# megacommand23-oledpowerfix.net
KiCad netlist of a schematic drawn in EAGLE
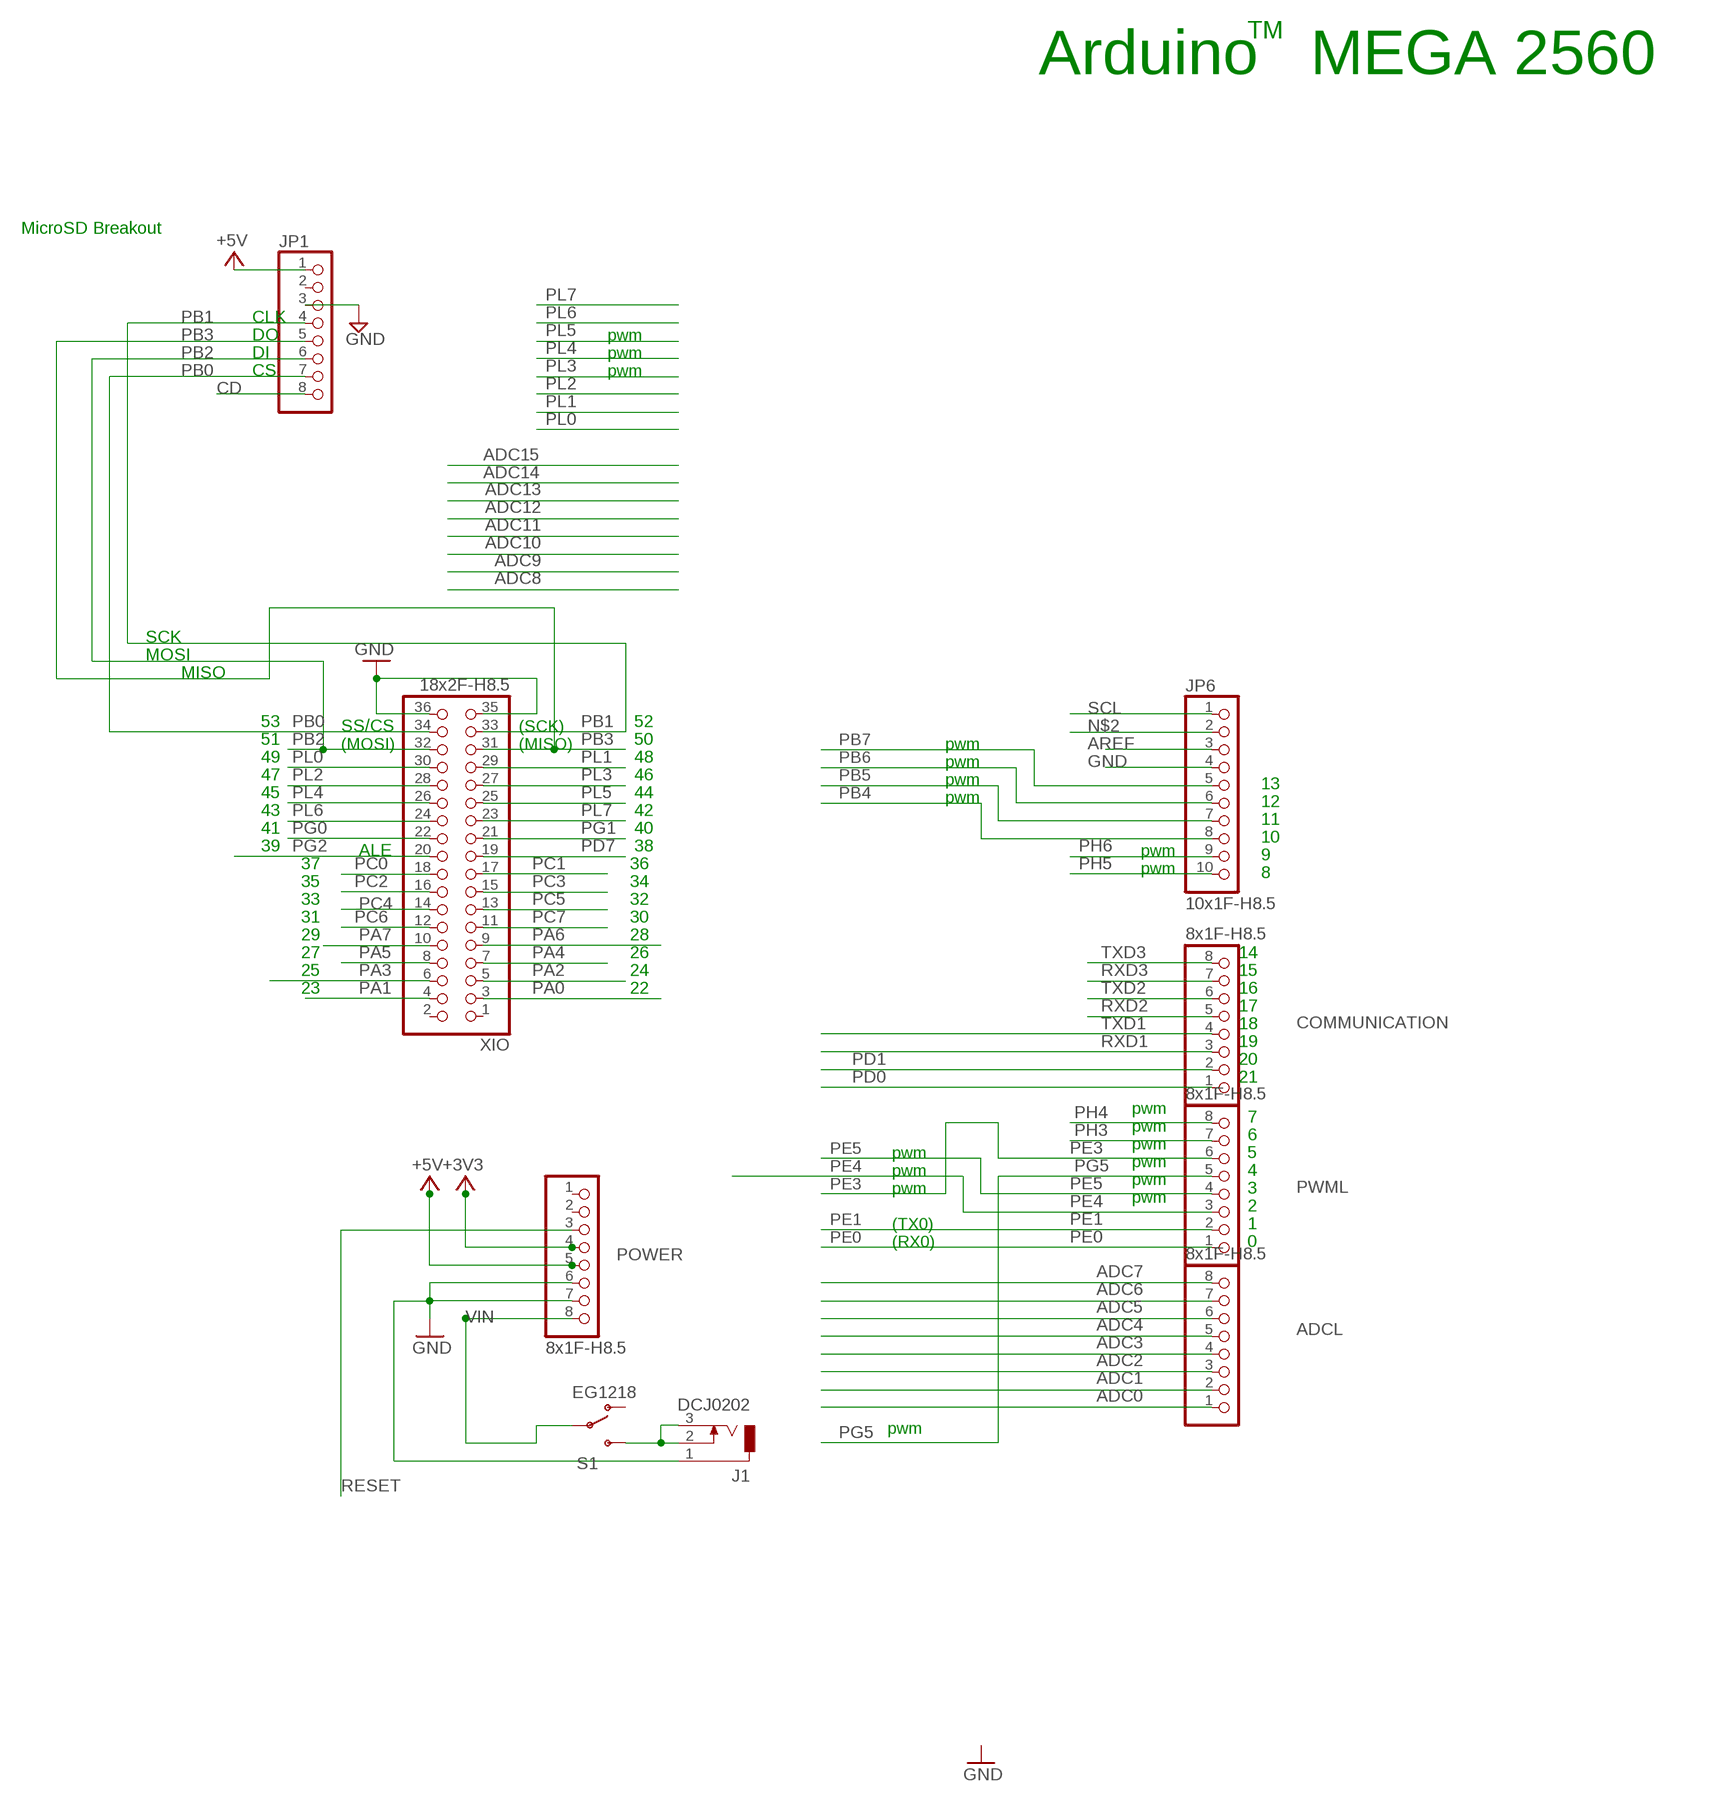
[diagram p0: schematic, sheet 1]
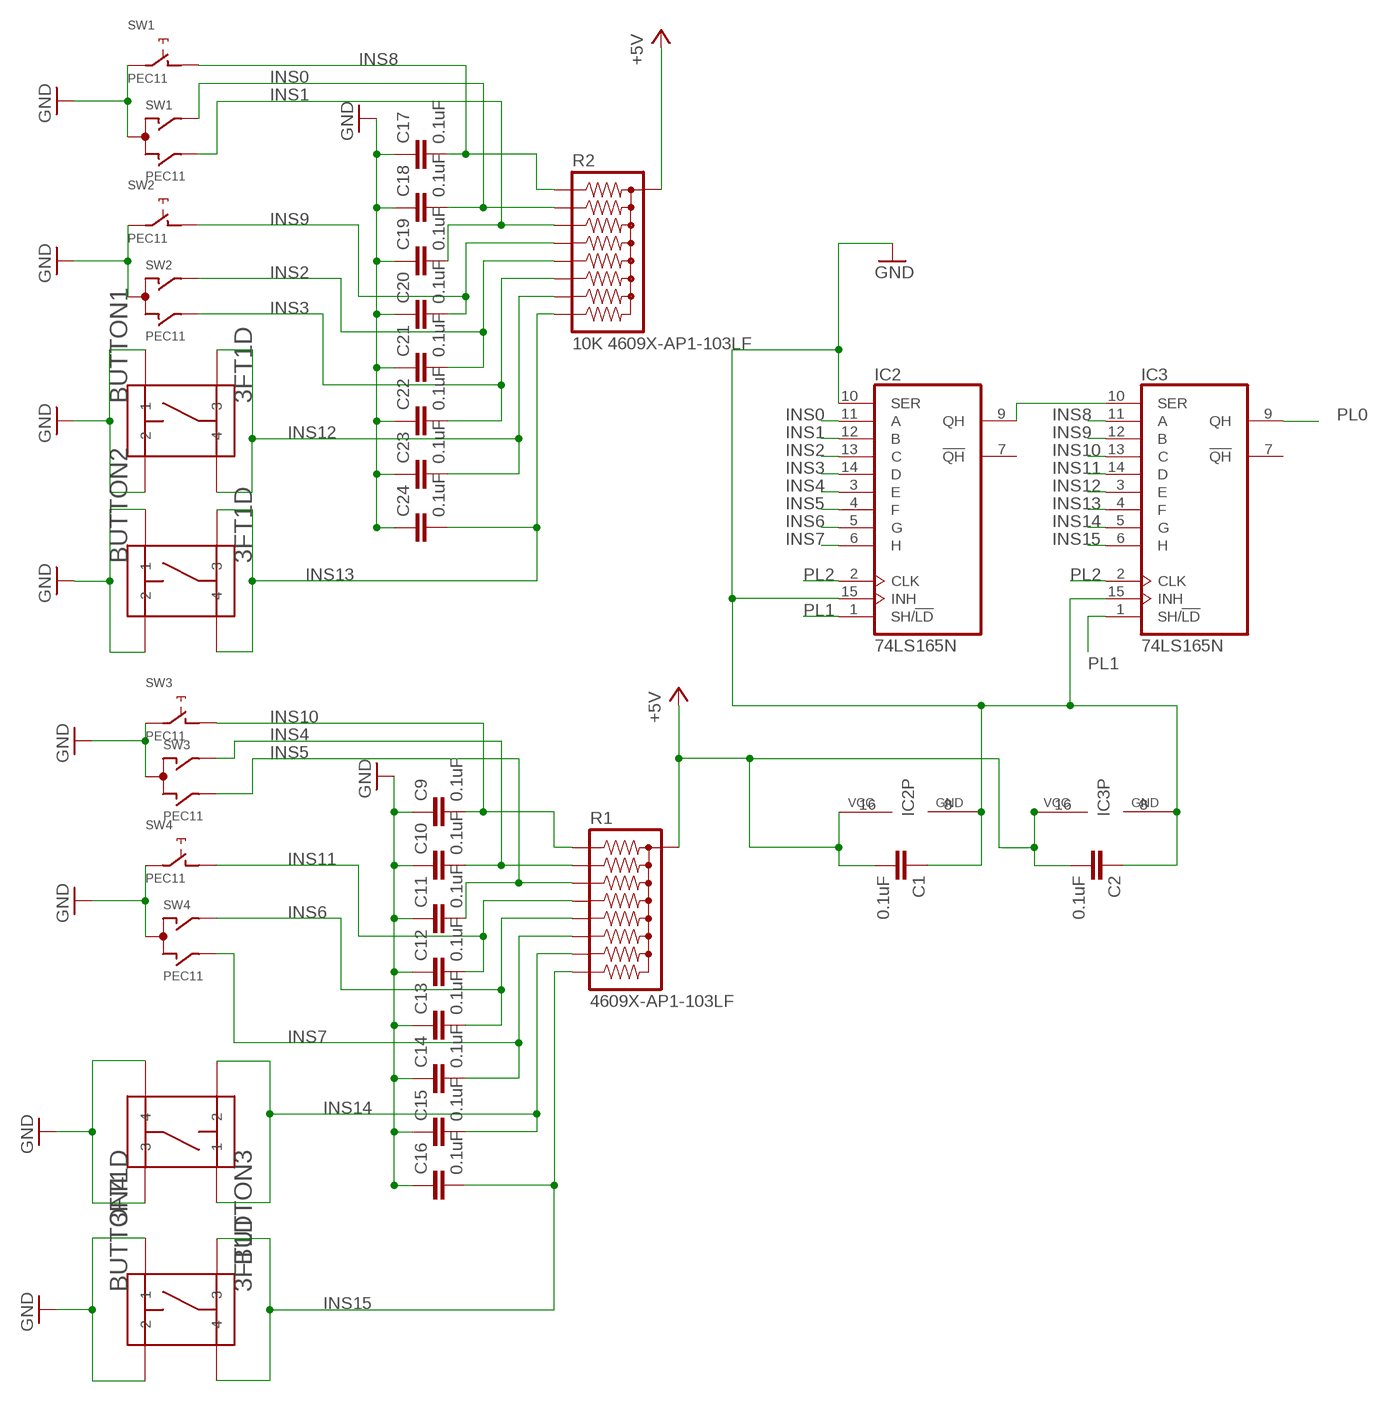
[diagram p1: schematic, sheet 2]
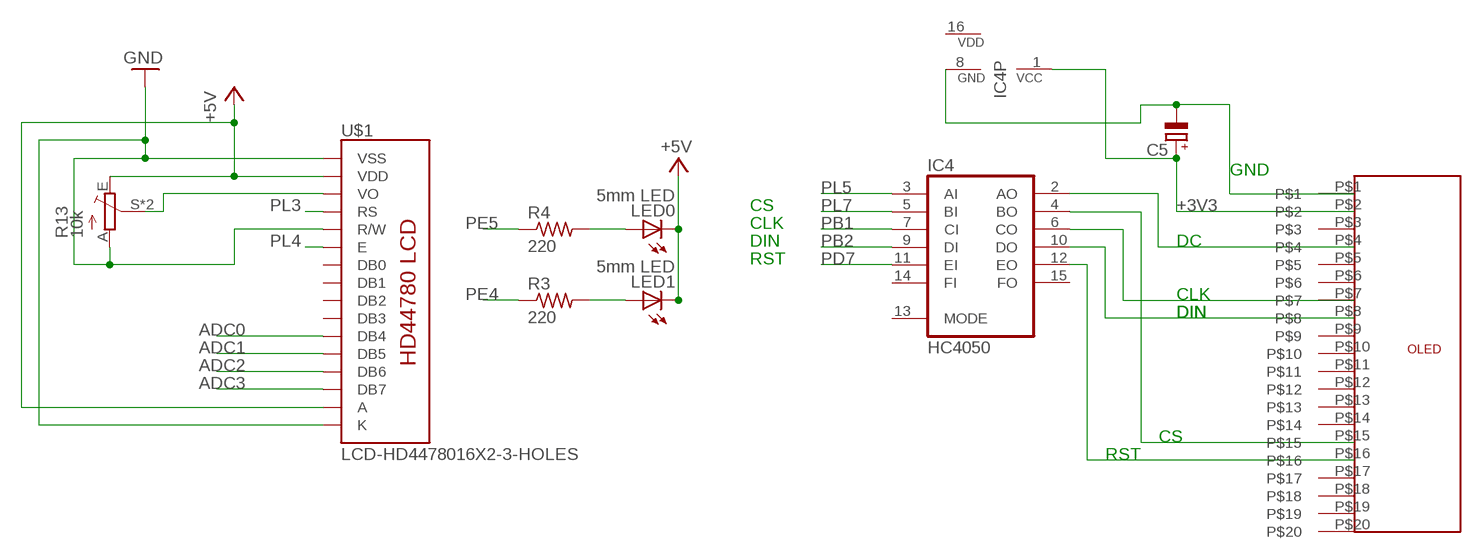
[diagram p2: schematic, sheet 3]
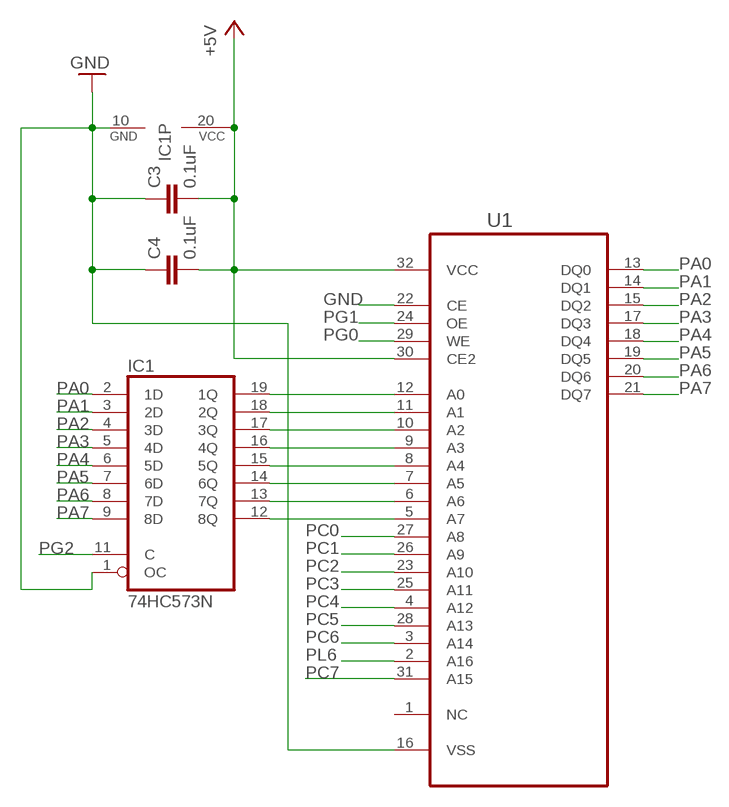
[diagram p3: schematic, sheet 4]
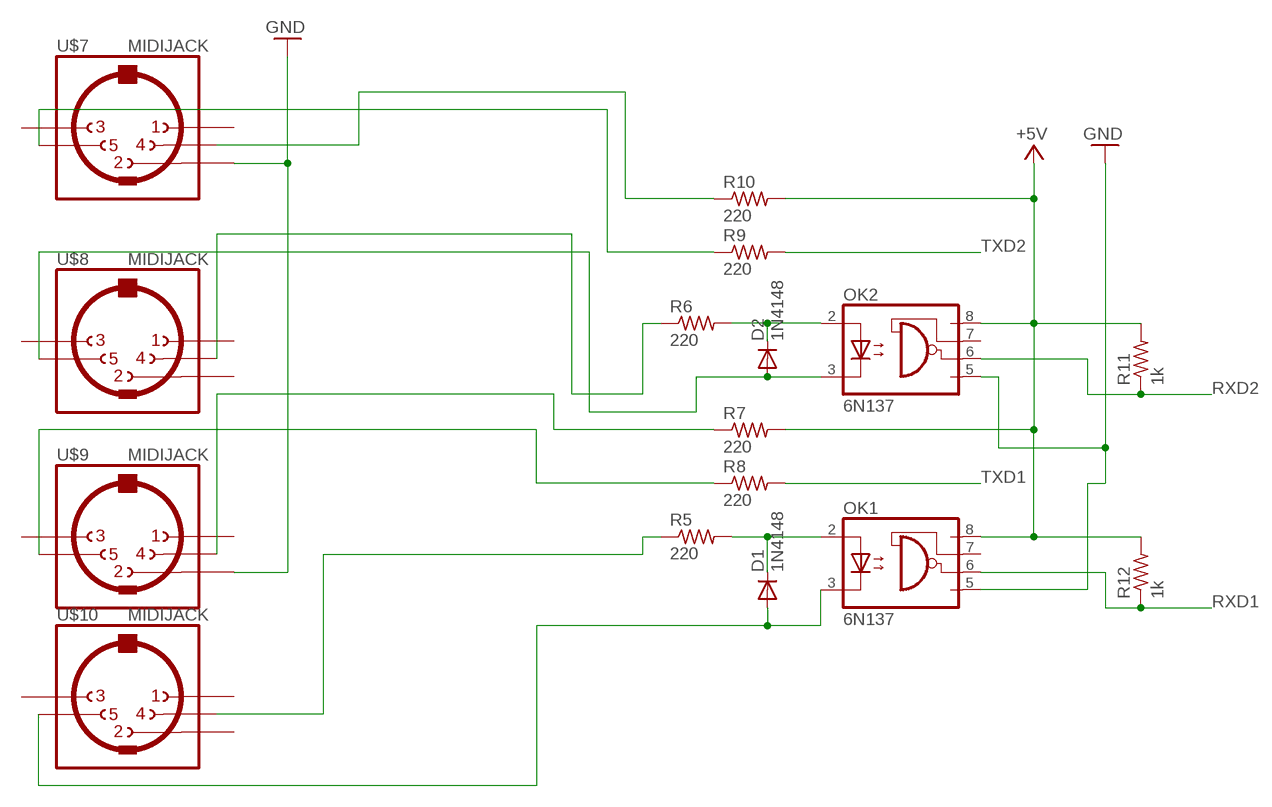
[diagram p4: schematic, sheet 5]

(export (version "E")
  (design (tool "Eeschema 10.0.6"))
  (components
    (comp (ref "C5")
      (value "CPOL-EUTT2D6")
      (footprint "eagle-import:TT2D6")
      (libsource (lib "eagle-import") (part "CPOL-EUTT2D6"))
    )
    (comp (ref "IC4")
      (value "HC4050")
      (footprint "eagle-import:DIL16")
      (libsource (lib "eagle-import") (part "4504N"))
    )
    (comp (ref "LED0")
      (value "5mm LED")
      (footprint "eagle-import:LED_LD260")
      (libsource (lib "eagle-import") (part "LED_ELD260"))
    )
    (comp (ref "LED1")
      (value "5mm LED")
      (footprint "eagle-import:LED_LD260")
      (libsource (lib "eagle-import") (part "LED_ELD260"))
    )
    (comp (ref "R3")
      (value "220")
      (footprint "eagle-import:0207_7")
      (libsource (lib "eagle-import") (part "R-US_0207/7"))
    )
    (comp (ref "R4")
      (value "220")
      (footprint "eagle-import:0207_7")
      (libsource (lib "eagle-import") (part "R-US_0207/7"))
    )
    (comp (ref "R13")
      (value "10k")
      (footprint "eagle-import:CA6V")
      (libsource (lib "eagle-import") (part "TRIM_EU-CA6V"))
    )
    (comp (ref "U$1")
      (value "LCD-HD4478016X2-3-HOLES")
      (footprint "eagle-import:LCD-16X2-3HOLES")
      (libsource (lib "eagle-import") (part "LCD-HD4478016X2-3-HOLES"))
    )
    (comp (ref "U$2")
      (value "20PIN")
      (footprint "eagle-import:20PIN")
      (libsource (lib "eagle-import") (part "20PIN"))
    )
    (comp (ref "D1")
      (value "1N4148")
      (footprint "eagle-import:DO35-7")
      (libsource (lib "eagle-import") (part "1N4148DO35-7"))
    )
    (comp (ref "D2")
      (value "1N4148")
      (footprint "eagle-import:DO35-7")
      (libsource (lib "eagle-import") (part "1N4148DO35-7"))
    )
    (comp (ref "OK1")
      (value "6N137")
      (footprint "eagle-import:DIL08")
      (libsource (lib "eagle-import") (part "6N137"))
    )
    (comp (ref "OK2")
      (value "6N137")
      (footprint "eagle-import:DIL08")
      (libsource (lib "eagle-import") (part "6N137"))
    )
    (comp (ref "R5")
      (value "220")
      (footprint "eagle-import:0207_7")
      (libsource (lib "eagle-import") (part "R-US_0207/7"))
    )
    (comp (ref "R6")
      (value "220")
      (footprint "eagle-import:0207_7")
      (libsource (lib "eagle-import") (part "R-US_0207/7"))
    )
    (comp (ref "R7")
      (value "220")
      (footprint "eagle-import:0207_7")
      (libsource (lib "eagle-import") (part "R-US_0207/7"))
    )
    (comp (ref "R8")
      (value "220")
      (footprint "eagle-import:0207_7")
      (libsource (lib "eagle-import") (part "R-US_0207/7"))
    )
    (comp (ref "R9")
      (value "220")
      (footprint "eagle-import:0207_7")
      (libsource (lib "eagle-import") (part "R-US_0207/7"))
    )
    (comp (ref "R10")
      (value "220")
      (footprint "eagle-import:0207_7")
      (libsource (lib "eagle-import") (part "R-US_0207/7"))
    )
    (comp (ref "R11")
      (value "1k")
      (footprint "eagle-import:0207_7")
      (libsource (lib "eagle-import") (part "R-US_0207/7"))
    )
    (comp (ref "R12")
      (value "1k")
      (footprint "eagle-import:0207_7")
      (libsource (lib "eagle-import") (part "R-US_0207/7"))
    )
    (comp (ref "U$7")
      (value "MIDIJACK")
      (footprint "eagle-import:CP-2350")
      (libsource (lib "eagle-import") (part "MIDIJACK"))
    )
    (comp (ref "U$8")
      (value "MIDIJACK")
      (footprint "eagle-import:CP-2350")
      (libsource (lib "eagle-import") (part "MIDIJACK"))
    )
    (comp (ref "U$9")
      (value "MIDIJACK")
      (footprint "eagle-import:CP-2350")
      (libsource (lib "eagle-import") (part "MIDIJACK"))
    )
    (comp (ref "U$10")
      (value "MIDIJACK")
      (footprint "eagle-import:CP-2350")
      (libsource (lib "eagle-import") (part "MIDIJACK"))
    )
    (comp (ref "BUTTON1")
      (value "3FT1D")
      (footprint "eagle-import:3FT")
      (libsource (lib "eagle-import") (part "3FT1D"))
    )
    (comp (ref "BUTTON2")
      (value "3FT1D")
      (footprint "eagle-import:3FT")
      (libsource (lib "eagle-import") (part "3FT1D"))
    )
    (comp (ref "BUTTON3")
      (value "3FT1D")
      (footprint "eagle-import:3FT")
      (libsource (lib "eagle-import") (part "3FT1D"))
    )
    (comp (ref "BUTTON4")
      (value "3FT1D")
      (footprint "eagle-import:3FT")
      (libsource (lib "eagle-import") (part "3FT1D"))
    )
    (comp (ref "C1")
      (value "0.1uF")
      (footprint "eagle-import:C025-050X050")
      (libsource (lib "eagle-import") (part "C-EU025-050X050"))
    )
    (comp (ref "C2")
      (value "0.1uF")
      (footprint "eagle-import:C025-050X050")
      (libsource (lib "eagle-import") (part "C-EU025-050X050"))
    )
    (comp (ref "C9")
      (value "0.1uF")
      (footprint "eagle-import:C025-050X050")
      (libsource (lib "eagle-import") (part "C-EU025-050X050"))
    )
    (comp (ref "C10")
      (value "0.1uF")
      (footprint "eagle-import:C025-050X050")
      (libsource (lib "eagle-import") (part "C-EU025-050X050"))
    )
    (comp (ref "C11")
      (value "0.1uF")
      (footprint "eagle-import:C025-050X050")
      (libsource (lib "eagle-import") (part "C-EU025-050X050"))
    )
    (comp (ref "C12")
      (value "0.1uF")
      (footprint "eagle-import:C025-050X050")
      (libsource (lib "eagle-import") (part "C-EU025-050X050"))
    )
    (comp (ref "C13")
      (value "0.1uF")
      (footprint "eagle-import:C025-050X050")
      (libsource (lib "eagle-import") (part "C-EU025-050X050"))
    )
    (comp (ref "C14")
      (value "0.1uF")
      (footprint "eagle-import:C025-050X050")
      (libsource (lib "eagle-import") (part "C-EU025-050X050"))
    )
    (comp (ref "C15")
      (value "0.1uF")
      (footprint "eagle-import:C025-050X050")
      (libsource (lib "eagle-import") (part "C-EU025-050X050"))
    )
    (comp (ref "C16")
      (value "0.1uF")
      (footprint "eagle-import:C025-050X050")
      (libsource (lib "eagle-import") (part "C-EU025-050X050"))
    )
    (comp (ref "C17")
      (value "0.1uF")
      (footprint "eagle-import:C025-050X050")
      (libsource (lib "eagle-import") (part "C-EU025-050X050"))
    )
    (comp (ref "C18")
      (value "0.1uF")
      (footprint "eagle-import:C025-050X050")
      (libsource (lib "eagle-import") (part "C-EU025-050X050"))
    )
    (comp (ref "C19")
      (value "0.1uF")
      (footprint "eagle-import:C025-050X050")
      (libsource (lib "eagle-import") (part "C-EU025-050X050"))
    )
    (comp (ref "C20")
      (value "0.1uF")
      (footprint "eagle-import:C025-050X050")
      (libsource (lib "eagle-import") (part "C-EU025-050X050"))
    )
    (comp (ref "C21")
      (value "0.1uF")
      (footprint "eagle-import:C025-050X050")
      (libsource (lib "eagle-import") (part "C-EU025-050X050"))
    )
    (comp (ref "C22")
      (value "0.1uF")
      (footprint "eagle-import:C025-050X050")
      (libsource (lib "eagle-import") (part "C-EU025-050X050"))
    )
    (comp (ref "C23")
      (value "0.1uF")
      (footprint "eagle-import:C025-050X050")
      (libsource (lib "eagle-import") (part "C-EU025-050X050"))
    )
    (comp (ref "C24")
      (value "0.1uF")
      (footprint "eagle-import:C025-050X050")
      (libsource (lib "eagle-import") (part "C-EU025-050X050"))
    )
    (comp (ref "IC2")
      (value "74LS165N")
      (footprint "eagle-import:DIL16")
      (libsource (lib "eagle-import") (part "74165NLS"))
    )
    (comp (ref "IC3")
      (value "74LS165N")
      (footprint "eagle-import:DIL16")
      (libsource (lib "eagle-import") (part "74165NLS"))
    )
    (comp (ref "R1")
      (value "4609X-AP1-103LF")
      (footprint "eagle-import:RPACK-SIP-PTH-8")
      (libsource (lib "eagle-import") (part "RPACK-BUSSED-8-SIP-PTH-8"))
    )
    (comp (ref "R2")
      (value "10K 4609X-AP1-103LF")
      (footprint "eagle-import:RPACK-SIP-PTH-8")
      (libsource (lib "eagle-import") (part "RPACK-BUSSED-8-SIP-PTH-8"))
    )
    (comp (ref "SW1")
      (value "PEC11")
      (footprint "eagle-import:ALPS_EC12E_SW")
      (fields (field (name "MPN") "EC12E2424407"))
      (libsource (lib "eagle-import") (part "EC12E_SW"))
    )
    (comp (ref "SW2")
      (value "PEC11")
      (footprint "eagle-import:ALPS_EC12E_SW")
      (fields (field (name "MPN") "EC12E2424407"))
      (libsource (lib "eagle-import") (part "EC12E_SW"))
    )
    (comp (ref "SW3")
      (value "PEC11")
      (footprint "eagle-import:ALPS_EC12E_SW")
      (fields (field (name "MPN") "EC12E2424407"))
      (libsource (lib "eagle-import") (part "EC12E_SW"))
    )
    (comp (ref "SW4")
      (value "PEC11")
      (footprint "eagle-import:ALPS_EC12E_SW")
      (fields (field (name "MPN") "EC12E2424407"))
      (libsource (lib "eagle-import") (part "EC12E_SW"))
    )
    (comp (ref "C3")
      (value "0.1uF")
      (footprint "eagle-import:C025-050X050")
      (libsource (lib "eagle-import") (part "C-EU025-050X050"))
    )
    (comp (ref "C4")
      (value "0.1uF")
      (footprint "eagle-import:C025-050X050")
      (libsource (lib "eagle-import") (part "C-EU025-050X050"))
    )
    (comp (ref "IC1")
      (value "74HC573N")
      (footprint "eagle-import:DIL20")
      (libsource (lib "eagle-import") (part "74573NHC"))
    )
    (comp (ref "U1")
      (value "AS6C1008-55PCN")
      (footprint "eagle-import:DIP254P1524X393-32")
      (libsource (lib "eagle-import") (part "AS6C1008-55PCN"))
    )
    (comp (ref "ADCL")
      (value "8x1F-H8.5")
      (footprint "eagle-import:1X08")
      (libsource (lib "eagle-import") (part "PINHD-1X8"))
    )
    (comp (ref "COMMUNICATION")
      (value "8x1F-H8.5")
      (footprint "eagle-import:1X08")
      (libsource (lib "eagle-import") (part "PINHD-1X8"))
    )
    (comp (ref "J1")
      (value "DCJ0202")
      (footprint "eagle-import:DCJ0202")
      (libsource (lib "eagle-import") (part "DCJ0202"))
    )
    (comp (ref "JP1")
      (value "PINHD-1X8BIG")
      (footprint "eagle-import:1X08-BIG")
      (libsource (lib "eagle-import") (part "PINHD-1X8BIG"))
    )
    (comp (ref "JP6")
      (value "10x1F-H8.5")
      (footprint "eagle-import:1X10")
      (libsource (lib "eagle-import") (part "PINHD-1X10_ARD"))
    )
    (comp (ref "POWER")
      (value "8x1F-H8.5")
      (footprint "eagle-import:1X08")
      (libsource (lib "eagle-import") (part "PINHD-1X8"))
    )
    (comp (ref "PWML")
      (value "8x1F-H8.5")
      (footprint "eagle-import:1X08")
      (libsource (lib "eagle-import") (part "PINHD-1X8"))
    )
    (comp (ref "S1")
      (value "EG1218")
      (footprint "eagle-import:SWITCH-SPDT_KIT")
      (libsource (lib "eagle-import") (part "SWITCH-SPDTKIT"))
    )
    (comp (ref "XIO")
      (value "18x2F-H8.5")
      (footprint "eagle-import:2X18")
      (libsource (lib "eagle-import") (part "PINHD-2X18"))
    )
  )
  (nets
    (net (code "1") (name "+3V3") (class "Default")
      (node (ref "C5") (pin "+") (pinfunction "+_+") (pintype "passive"))
      (node (ref "IC4") (pin "1") (pinfunction "VCC_1") (pintype "power_in"))
      (node (ref "POWER") (pin "4") (pinfunction "4_4") (pintype "passive"))
      (node (ref "U$2") (pin "P$2") (pinfunction "P$2_P$2") (pintype "bidirectional"))
    )
    (net (code "2") (name "+5V") (class "Default")
      (node (ref "C1") (pin "2") (pinfunction "2_2") (pintype "passive"))
      (node (ref "C2") (pin "2") (pinfunction "2_2") (pintype "passive"))
      (node (ref "C3") (pin "2") (pinfunction "2_2") (pintype "passive"))
      (node (ref "C4") (pin "2") (pinfunction "2_2") (pintype "passive"))
      (node (ref "IC1") (pin "20") (pinfunction "VCC_20") (pintype "power_in"))
      (node (ref "IC2") (pin "16") (pinfunction "VCC_16") (pintype "power_in"))
      (node (ref "IC3") (pin "16") (pinfunction "VCC_16") (pintype "power_in"))
      (node (ref "JP1") (pin "1") (pinfunction "1_1") (pintype "passive"))
      (node (ref "LED0") (pin "K") (pinfunction "C_K") (pintype "passive"))
      (node (ref "LED1") (pin "K") (pinfunction "C_K") (pintype "passive"))
      (node (ref "OK1") (pin "8") (pinfunction "VCC_8") (pintype "passive"))
      (node (ref "OK2") (pin "8") (pinfunction "VCC_8") (pintype "passive"))
      (node (ref "POWER") (pin "5") (pinfunction "5_5") (pintype "passive"))
      (node (ref "R1") (pin "P$1") (pinfunction "1_P$1") (pintype "passive"))
      (node (ref "R10") (pin "2") (pinfunction "2_2") (pintype "passive"))
      (node (ref "R11") (pin "2") (pinfunction "2_2") (pintype "passive"))
      (node (ref "R12") (pin "2") (pinfunction "2_2") (pintype "passive"))
      (node (ref "R13") (pin "E") (pinfunction "E_E") (pintype "passive"))
      (node (ref "R2") (pin "P$1") (pinfunction "1_P$1") (pintype "passive"))
      (node (ref "R7") (pin "2") (pinfunction "2_2") (pintype "passive"))
      (node (ref "U$1") (pin "15") (pinfunction "A_15") (pintype "power_in"))
      (node (ref "U$1") (pin "2") (pinfunction "VDD_2") (pintype "power_in"))
      (node (ref "U1") (pin "30") (pinfunction "CE2_30") (pintype "input"))
      (node (ref "U1") (pin "32") (pinfunction "VCC_32") (pintype "power_in"))
    )
    (net (code "3") (name "ADC0") (class "Default")
      (node (ref "ADCL") (pin "1") (pinfunction "1_1") (pintype "passive"))
      (node (ref "U$1") (pin "11") (pinfunction "DB4_11") (pintype "bidirectional"))
    )
    (net (code "4") (name "ADC1") (class "Default")
      (node (ref "ADCL") (pin "2") (pinfunction "2_2") (pintype "passive"))
      (node (ref "U$1") (pin "12") (pinfunction "DB5_12") (pintype "bidirectional"))
    )
    (net (code "5") (name "ADC2") (class "Default")
      (node (ref "ADCL") (pin "3") (pinfunction "3_3") (pintype "passive"))
      (node (ref "U$1") (pin "13") (pinfunction "DB6_13") (pintype "bidirectional"))
    )
    (net (code "6") (name "ADC3") (class "Default")
      (node (ref "ADCL") (pin "4") (pinfunction "4_4") (pintype "passive"))
      (node (ref "U$1") (pin "14") (pinfunction "DB7_14") (pintype "bidirectional"))
    )
    (net (code "7") (name "ADC4") (class "Default")
      (node (ref "ADCL") (pin "5") (pinfunction "5_5") (pintype "passive"))
    )
    (net (code "8") (name "ADC5") (class "Default")
      (node (ref "ADCL") (pin "6") (pinfunction "6_6") (pintype "passive"))
    )
    (net (code "9") (name "ADC6") (class "Default")
      (node (ref "ADCL") (pin "7") (pinfunction "7_7") (pintype "passive"))
    )
    (net (code "10") (name "ADC7") (class "Default")
      (node (ref "ADCL") (pin "8") (pinfunction "8_8") (pintype "passive"))
    )
    (net (code "19") (name "AREF") (class "Default")
      (node (ref "JP6") (pin "3") (pinfunction "3_3") (pintype "passive"))
    )
    (net (code "20") (name "CD") (class "Default")
      (node (ref "JP1") (pin "8") (pinfunction "8_8") (pintype "passive"))
    )
    (net (code "21") (name "GND") (class "Default")
      (node (ref "BUTTON1") (pin "P$1") (pinfunction "1_P$1") (pintype "bidirectional"))
      (node (ref "BUTTON1") (pin "P$2") (pinfunction "2_P$2") (pintype "bidirectional"))
      (node (ref "BUTTON2") (pin "P$1") (pinfunction "1_P$1") (pintype "bidirectional"))
      (node (ref "BUTTON2") (pin "P$2") (pinfunction "2_P$2") (pintype "bidirectional"))
      (node (ref "BUTTON3") (pin "P$3") (pinfunction "3_P$3") (pintype "bidirectional"))
      (node (ref "BUTTON3") (pin "P$4") (pinfunction "4_P$4") (pintype "bidirectional"))
      (node (ref "BUTTON4") (pin "P$1") (pinfunction "1_P$1") (pintype "bidirectional"))
      (node (ref "BUTTON4") (pin "P$2") (pinfunction "2_P$2") (pintype "bidirectional"))
      (node (ref "C1") (pin "1") (pinfunction "1_1") (pintype "passive"))
      (node (ref "C10") (pin "1") (pinfunction "1_1") (pintype "passive"))
      (node (ref "C11") (pin "1") (pinfunction "1_1") (pintype "passive"))
      (node (ref "C12") (pin "1") (pinfunction "1_1") (pintype "passive"))
      (node (ref "C13") (pin "1") (pinfunction "1_1") (pintype "passive"))
      (node (ref "C14") (pin "1") (pinfunction "1_1") (pintype "passive"))
      (node (ref "C15") (pin "1") (pinfunction "1_1") (pintype "passive"))
      (node (ref "C16") (pin "1") (pinfunction "1_1") (pintype "passive"))
      (node (ref "C17") (pin "1") (pinfunction "1_1") (pintype "passive"))
      (node (ref "C18") (pin "1") (pinfunction "1_1") (pintype "passive"))
      (node (ref "C19") (pin "1") (pinfunction "1_1") (pintype "passive"))
      (node (ref "C2") (pin "1") (pinfunction "1_1") (pintype "passive"))
      (node (ref "C20") (pin "1") (pinfunction "1_1") (pintype "passive"))
      (node (ref "C21") (pin "1") (pinfunction "1_1") (pintype "passive"))
      (node (ref "C22") (pin "1") (pinfunction "1_1") (pintype "passive"))
      (node (ref "C23") (pin "1") (pinfunction "1_1") (pintype "passive"))
      (node (ref "C24") (pin "1") (pinfunction "1_1") (pintype "passive"))
      (node (ref "C3") (pin "1") (pinfunction "1_1") (pintype "passive"))
      (node (ref "C4") (pin "1") (pinfunction "1_1") (pintype "passive"))
      (node (ref "C5") (pin "-") (pinfunction "-_-") (pintype "passive"))
      (node (ref "C9") (pin "1") (pinfunction "1_1") (pintype "passive"))
      (node (ref "IC1") (pin "1") (pinfunction "OC_1") (pintype "input"))
      (node (ref "IC1") (pin "10") (pinfunction "GND_10") (pintype "power_in"))
      (node (ref "IC2") (pin "10") (pinfunction "SER_10") (pintype "input"))
      (node (ref "IC2") (pin "15") (pinfunction "INH_15") (pintype "input"))
      (node (ref "IC2") (pin "8") (pinfunction "GND_8") (pintype "power_in"))
      (node (ref "IC3") (pin "15") (pinfunction "INH_15") (pintype "input"))
      (node (ref "IC3") (pin "8") (pinfunction "GND_8") (pintype "power_in"))
      (node (ref "IC4") (pin "8") (pinfunction "GND_8") (pintype "power_in"))
      (node (ref "J1") (pin "1") (pinfunction "1_1") (pintype "passive"))
      (node (ref "JP1") (pin "3") (pinfunction "3_3") (pintype "passive"))
      (node (ref "JP6") (pin "4") (pinfunction "4_4") (pintype "passive"))
      (node (ref "OK1") (pin "5") (pinfunction "GND_5") (pintype "passive"))
      (node (ref "OK2") (pin "5") (pinfunction "GND_5") (pintype "passive"))
      (node (ref "POWER") (pin "6") (pinfunction "6_6") (pintype "passive"))
      (node (ref "POWER") (pin "7") (pinfunction "7_7") (pintype "passive"))
      (node (ref "R13") (pin "A") (pinfunction "A_A") (pintype "passive"))
      (node (ref "SW1") (pin "C") (pinfunction "C_C") (pintype "passive"))
      (node (ref "SW1") (pin "E") (pinfunction "2_E") (pintype "passive"))
      (node (ref "SW2") (pin "C") (pinfunction "C_C") (pintype "passive"))
      (node (ref "SW2") (pin "E") (pinfunction "2_E") (pintype "passive"))
      (node (ref "SW3") (pin "C") (pinfunction "C_C") (pintype "passive"))
      (node (ref "SW3") (pin "E") (pinfunction "2_E") (pintype "passive"))
      (node (ref "SW4") (pin "C") (pinfunction "C_C") (pintype "passive"))
      (node (ref "SW4") (pin "E") (pinfunction "2_E") (pintype "passive"))
      (node (ref "U$1") (pin "1") (pinfunction "VSS_1") (pintype "power_in"))
      (node (ref "U$1") (pin "16") (pinfunction "K_16") (pintype "power_in"))
      (node (ref "U$1") (pin "5") (pinfunction "R/W_5") (pintype "input"))
      (node (ref "U$2") (pin "P$1") (pinfunction "P$1_P$1") (pintype "bidirectional"))
      (node (ref "U$7") (pin "2") (pinfunction "2_2") (pintype "passive"))
      (node (ref "U$9") (pin "2") (pinfunction "2_2") (pintype "passive"))
      (node (ref "U1") (pin "16") (pinfunction "VSS_16") (pintype "bidirectional"))
      (node (ref "U1") (pin "22") (pinfunction "CE_22") (pintype "input"))
      (node (ref "XIO") (pin "35") (pinfunction "35_35") (pintype "passive"))
      (node (ref "XIO") (pin "36") (pinfunction "36_36") (pintype "passive"))
    )
    (net (code "22") (name "INS0") (class "Default")
      (node (ref "C18") (pin "2") (pinfunction "2_2") (pintype "passive"))
      (node (ref "IC2") (pin "11") (pinfunction "A_11") (pintype "input"))
      (node (ref "R2") (pin "P$3") (pinfunction "3_P$3") (pintype "passive"))
      (node (ref "SW1") (pin "A") (pinfunction "A_A") (pintype "passive"))
    )
    (net (code "23") (name "INS1") (class "Default")
      (node (ref "C19") (pin "2") (pinfunction "2_2") (pintype "passive"))
      (node (ref "IC2") (pin "12") (pinfunction "B_12") (pintype "input"))
      (node (ref "R2") (pin "P$4") (pinfunction "4_P$4") (pintype "passive"))
      (node (ref "SW1") (pin "B") (pinfunction "B_B") (pintype "passive"))
    )
    (net (code "24") (name "INS2") (class "Default")
      (node (ref "C21") (pin "2") (pinfunction "2_2") (pintype "passive"))
      (node (ref "IC2") (pin "13") (pinfunction "C_13") (pintype "input"))
      (node (ref "R2") (pin "P$6") (pinfunction "6_P$6") (pintype "passive"))
      (node (ref "SW2") (pin "A") (pinfunction "A_A") (pintype "passive"))
    )
    (net (code "25") (name "INS3") (class "Default")
      (node (ref "C22") (pin "2") (pinfunction "2_2") (pintype "passive"))
      (node (ref "IC2") (pin "14") (pinfunction "D_14") (pintype "input"))
      (node (ref "R2") (pin "P$7") (pinfunction "7_P$7") (pintype "passive"))
      (node (ref "SW2") (pin "B") (pinfunction "B_B") (pintype "passive"))
    )
    (net (code "26") (name "INS4") (class "Default")
      (node (ref "C10") (pin "2") (pinfunction "2_2") (pintype "passive"))
      (node (ref "IC2") (pin "3") (pinfunction "E_3") (pintype "input"))
      (node (ref "R1") (pin "P$3") (pinfunction "3_P$3") (pintype "passive"))
      (node (ref "SW3") (pin "A") (pinfunction "A_A") (pintype "passive"))
    )
    (net (code "27") (name "INS5") (class "Default")
      (node (ref "C11") (pin "2") (pinfunction "2_2") (pintype "passive"))
      (node (ref "IC2") (pin "4") (pinfunction "F_4") (pintype "input"))
      (node (ref "R1") (pin "P$4") (pinfunction "4_P$4") (pintype "passive"))
      (node (ref "SW3") (pin "B") (pinfunction "B_B") (pintype "passive"))
    )
    (net (code "28") (name "INS6") (class "Default")
      (node (ref "C13") (pin "2") (pinfunction "2_2") (pintype "passive"))
      (node (ref "IC2") (pin "5") (pinfunction "G_5") (pintype "input"))
      (node (ref "R1") (pin "P$6") (pinfunction "6_P$6") (pintype "passive"))
      (node (ref "SW4") (pin "A") (pinfunction "A_A") (pintype "passive"))
    )
    (net (code "29") (name "INS7") (class "Default")
      (node (ref "C14") (pin "2") (pinfunction "2_2") (pintype "passive"))
      (node (ref "IC2") (pin "6") (pinfunction "H_6") (pintype "input"))
      (node (ref "R1") (pin "P$7") (pinfunction "7_P$7") (pintype "passive"))
      (node (ref "SW4") (pin "B") (pinfunction "B_B") (pintype "passive"))
    )
    (net (code "30") (name "INS8") (class "Default")
      (node (ref "C17") (pin "2") (pinfunction "2_2") (pintype "passive"))
      (node (ref "IC3") (pin "11") (pinfunction "A_11") (pintype "input"))
      (node (ref "R2") (pin "P$2") (pinfunction "2_P$2") (pintype "passive"))
      (node (ref "SW1") (pin "D") (pinfunction "1_D") (pintype "passive"))
    )
    (net (code "31") (name "INS9") (class "Default")
      (node (ref "C20") (pin "2") (pinfunction "2_2") (pintype "passive"))
      (node (ref "IC3") (pin "12") (pinfunction "B_12") (pintype "input"))
      (node (ref "R2") (pin "P$5") (pinfunction "5_P$5") (pintype "passive"))
      (node (ref "SW2") (pin "D") (pinfunction "1_D") (pintype "passive"))
    )
    (net (code "32") (name "INS10") (class "Default")
      (node (ref "C9") (pin "2") (pinfunction "2_2") (pintype "passive"))
      (node (ref "IC3") (pin "13") (pinfunction "C_13") (pintype "input"))
      (node (ref "R1") (pin "P$2") (pinfunction "2_P$2") (pintype "passive"))
      (node (ref "SW3") (pin "D") (pinfunction "1_D") (pintype "passive"))
    )
    (net (code "33") (name "INS11") (class "Default")
      (node (ref "C12") (pin "2") (pinfunction "2_2") (pintype "passive"))
      (node (ref "IC3") (pin "14") (pinfunction "D_14") (pintype "input"))
      (node (ref "R1") (pin "P$5") (pinfunction "5_P$5") (pintype "passive"))
      (node (ref "SW4") (pin "D") (pinfunction "1_D") (pintype "passive"))
    )
    (net (code "34") (name "INS12") (class "Default")
      (node (ref "BUTTON1") (pin "P$3") (pinfunction "3_P$3") (pintype "bidirectional"))
      (node (ref "BUTTON1") (pin "P$4") (pinfunction "4_P$4") (pintype "bidirectional"))
      (node (ref "C23") (pin "2") (pinfunction "2_2") (pintype "passive"))
      (node (ref "IC3") (pin "3") (pinfunction "E_3") (pintype "input"))
      (node (ref "R2") (pin "P$8") (pinfunction "8_P$8") (pintype "passive"))
    )
    (net (code "35") (name "INS13") (class "Default")
      (node (ref "BUTTON2") (pin "P$3") (pinfunction "3_P$3") (pintype "bidirectional"))
      (node (ref "BUTTON2") (pin "P$4") (pinfunction "4_P$4") (pintype "bidirectional"))
      (node (ref "C24") (pin "2") (pinfunction "2_2") (pintype "passive"))
      (node (ref "IC3") (pin "4") (pinfunction "F_4") (pintype "input"))
      (node (ref "R2") (pin "P$9") (pinfunction "9_P$9") (pintype "passive"))
    )
    (net (code "36") (name "INS14") (class "Default")
      (node (ref "BUTTON3") (pin "P$1") (pinfunction "1_P$1") (pintype "bidirectional"))
      (node (ref "BUTTON3") (pin "P$2") (pinfunction "2_P$2") (pintype "bidirectional"))
      (node (ref "C15") (pin "2") (pinfunction "2_2") (pintype "passive"))
      (node (ref "IC3") (pin "5") (pinfunction "G_5") (pintype "input"))
      (node (ref "R1") (pin "P$8") (pinfunction "8_P$8") (pintype "passive"))
    )
    (net (code "37") (name "INS15") (class "Default")
      (node (ref "BUTTON4") (pin "P$3") (pinfunction "3_P$3") (pintype "bidirectional"))
      (node (ref "BUTTON4") (pin "P$4") (pinfunction "4_P$4") (pintype "bidirectional"))
      (node (ref "C16") (pin "2") (pinfunction "2_2") (pintype "passive"))
      (node (ref "IC3") (pin "6") (pinfunction "H_6") (pintype "input"))
      (node (ref "R1") (pin "P$9") (pinfunction "9_P$9") (pintype "passive"))
    )
    (net (code "38") (name "N$2") (class "Default")
      (node (ref "JP6") (pin "2") (pinfunction "2_2") (pintype "passive"))
    )
    (net (code "39") (name "Net-(IC1A-1Q)") (class "Default")
      (node (ref "IC1") (pin "19") (pinfunction "1Q_19") (pintype "tri_state"))
      (node (ref "U1") (pin "12") (pinfunction "A0_12") (pintype "input"))
    )
    (net (code "40") (name "Net-(IC1A-2Q)") (class "Default")
      (node (ref "IC1") (pin "18") (pinfunction "2Q_18") (pintype "tri_state"))
      (node (ref "U1") (pin "11") (pinfunction "A1_11") (pintype "input"))
    )
    (net (code "41") (name "Net-(IC1A-3Q)") (class "Default")
      (node (ref "IC1") (pin "17") (pinfunction "3Q_17") (pintype "tri_state"))
      (node (ref "U1") (pin "10") (pinfunction "A2_10") (pintype "input"))
    )
    (net (code "42") (name "Net-(IC1A-4Q)") (class "Default")
      (node (ref "IC1") (pin "16") (pinfunction "4Q_16") (pintype "tri_state"))
      (node (ref "U1") (pin "9") (pinfunction "A3_9") (pintype "input"))
    )
    (net (code "43") (name "Net-(IC1A-5Q)") (class "Default")
      (node (ref "IC1") (pin "15") (pinfunction "5Q_15") (pintype "tri_state"))
      (node (ref "U1") (pin "8") (pinfunction "A4_8") (pintype "input"))
    )
    (net (code "44") (name "Net-(IC1A-6Q)") (class "Default")
      (node (ref "IC1") (pin "14") (pinfunction "6Q_14") (pintype "tri_state"))
      (node (ref "U1") (pin "7") (pinfunction "A5_7") (pintype "input"))
    )
    (net (code "45") (name "Net-(IC1A-7Q)") (class "Default")
      (node (ref "IC1") (pin "13") (pinfunction "7Q_13") (pintype "tri_state"))
      (node (ref "U1") (pin "6") (pinfunction "A6_6") (pintype "input"))
    )
    (net (code "46") (name "Net-(IC1A-8Q)") (class "Default")
      (node (ref "IC1") (pin "12") (pinfunction "8Q_12") (pintype "tri_state"))
      (node (ref "U1") (pin "5") (pinfunction "A7_5") (pintype "input"))
    )
    (net (code "47") (name "Net-(IC2A-QH)") (class "Default")
      (node (ref "IC2") (pin "9") (pinfunction "QH_9") (pintype "output"))
      (node (ref "IC3") (pin "10") (pinfunction "SER_10") (pintype "input"))
    )
    (net (code "48") (name "Net-(IC4A-AO)") (class "Default")
      (node (ref "IC4") (pin "2") (pinfunction "AO_2") (pintype "output"))
      (node (ref "U$2") (pin "P$4") (pinfunction "P$4_P$4") (pintype "bidirectional"))
    )
    (net (code "49") (name "Net-(IC4A-BO)") (class "Default")
      (node (ref "IC4") (pin "4") (pinfunction "BO_4") (pintype "output"))
      (node (ref "U$2") (pin "P$15") (pinfunction "P$15_P$15") (pintype "bidirectional"))
    )
    (net (code "50") (name "Net-(IC4A-CO)") (class "Default")
      (node (ref "IC4") (pin "6") (pinfunction "CO_6") (pintype "output"))
      (node (ref "U$2") (pin "P$7") (pinfunction "P$7_P$7") (pintype "bidirectional"))
    )
    (net (code "51") (name "Net-(IC4A-DO)") (class "Default")
      (node (ref "IC4") (pin "10") (pinfunction "DO_10") (pintype "output"))
      (node (ref "U$2") (pin "P$8") (pinfunction "P$8_P$8") (pintype "bidirectional"))
    )
    (net (code "52") (name "Net-(IC4A-EO)") (class "Default")
      (node (ref "IC4") (pin "12") (pinfunction "EO_12") (pintype "output"))
      (node (ref "U$2") (pin "P$16") (pinfunction "P$16_P$16") (pintype "bidirectional"))
    )
    (net (code "53") (name "Net-(LED0-PadA)") (class "Default")
      (node (ref "LED0") (pin "A") (pinfunction "A_A") (pintype "passive"))
      (node (ref "R4") (pin "2") (pinfunction "2_2") (pintype "passive"))
    )
    (net (code "54") (name "Net-(LED1-PadA)") (class "Default")
      (node (ref "LED1") (pin "A") (pinfunction "A_A") (pintype "passive"))
      (node (ref "R3") (pin "2") (pinfunction "2_2") (pintype "passive"))
    )
    (net (code "55") (name "Net-(OK1-A)") (class "Default")
      (node (ref "D1") (pin "C") (pinfunction "C_C") (pintype "passive"))
      (node (ref "OK1") (pin "2") (pinfunction "A_2") (pintype "passive"))
      (node (ref "R5") (pin "2") (pinfunction "2_2") (pintype "passive"))
    )
    (net (code "56") (name "Net-(OK1-C)") (class "Default")
      (node (ref "D1") (pin "A") (pinfunction "A_A") (pintype "passive"))
      (node (ref "OK1") (pin "3") (pinfunction "C_3") (pintype "passive"))
      (node (ref "U$10") (pin "5") (pinfunction "5_5") (pintype "passive"))
    )
    (net (code "57") (name "Net-(OK2-A)") (class "Default")
      (node (ref "D2") (pin "C") (pinfunction "C_C") (pintype "passive"))
      (node (ref "OK2") (pin "2") (pinfunction "A_2") (pintype "passive"))
      (node (ref "R6") (pin "2") (pinfunction "2_2") (pintype "passive"))
    )
    (net (code "58") (name "Net-(OK2-C)") (class "Default")
      (node (ref "D2") (pin "A") (pinfunction "A_A") (pintype "passive"))
      (node (ref "OK2") (pin "3") (pinfunction "C_3") (pintype "passive"))
      (node (ref "U$8") (pin "5") (pinfunction "5_5") (pintype "passive"))
    )
    (net (code "59") (name "Net-(R5-Pad1)") (class "Default")
      (node (ref "R5") (pin "1") (pinfunction "1_1") (pintype "passive"))
      (node (ref "U$10") (pin "4") (pinfunction "4_4") (pintype "passive"))
    )
    (net (code "60") (name "Net-(R6-Pad1)") (class "Default")
      (node (ref "R6") (pin "1") (pinfunction "1_1") (pintype "passive"))
      (node (ref "U$8") (pin "4") (pinfunction "4_4") (pintype "passive"))
    )
    (net (code "61") (name "Net-(R7-Pad1)") (class "Default")
      (node (ref "R7") (pin "1") (pinfunction "1_1") (pintype "passive"))
      (node (ref "U$9") (pin "4") (pinfunction "4_4") (pintype "passive"))
    )
    (net (code "62") (name "Net-(R8-Pad1)") (class "Default")
      (node (ref "R8") (pin "1") (pinfunction "1_1") (pintype "passive"))
      (node (ref "U$9") (pin "5") (pinfunction "5_5") (pintype "passive"))
    )
    (net (code "63") (name "Net-(R9-Pad1)") (class "Default")
      (node (ref "R9") (pin "1") (pinfunction "1_1") (pintype "passive"))
      (node (ref "U$7") (pin "5") (pinfunction "5_5") (pintype "passive"))
    )
    (net (code "64") (name "Net-(R10-Pad1)") (class "Default")
      (node (ref "R10") (pin "1") (pinfunction "1_1") (pintype "passive"))
      (node (ref "U$7") (pin "4") (pinfunction "4_4") (pintype "passive"))
    )
    (net (code "65") (name "Net-(S1-S)") (class "Default")
      (node (ref "J1") (pin "2") (pinfunction "2_2") (pintype "passive"))
      (node (ref "J1") (pin "3") (pinfunction "3_3") (pintype "passive"))
      (node (ref "S1") (pin "3") (pinfunction "S_3") (pintype "passive"))
    )
    (net (code "66") (name "Net-(U$1-VO)") (class "Default")
      (node (ref "R13") (pin "S") (pinfunction "S_S") (pintype "passive"))
      (node (ref "R13") (pin "S1") (pinfunction "S_S1") (pintype "passive"))
      (node (ref "U$1") (pin "3") (pinfunction "VO_3") (pintype "bidirectional"))
    )
    (net (code "67") (name "PA0") (class "Default")
      (node (ref "IC1") (pin "2") (pinfunction "1D_2") (pintype "input"))
      (node (ref "U1") (pin "13") (pinfunction "DQ0_13") (pintype "bidirectional"))
      (node (ref "XIO") (pin "3") (pinfunction "3_3") (pintype "passive"))
    )
    (net (code "68") (name "PA1") (class "Default")
      (node (ref "IC1") (pin "3") (pinfunction "2D_3") (pintype "input"))
      (node (ref "U1") (pin "14") (pinfunction "DQ1_14") (pintype "bidirectional"))
      (node (ref "XIO") (pin "4") (pinfunction "4_4") (pintype "passive"))
    )
    (net (code "69") (name "PA2") (class "Default")
      (node (ref "IC1") (pin "4") (pinfunction "3D_4") (pintype "input"))
      (node (ref "U1") (pin "15") (pinfunction "DQ2_15") (pintype "bidirectional"))
      (node (ref "XIO") (pin "5") (pinfunction "5_5") (pintype "passive"))
    )
    (net (code "70") (name "PA3") (class "Default")
      (node (ref "IC1") (pin "5") (pinfunction "4D_5") (pintype "input"))
      (node (ref "U1") (pin "17") (pinfunction "DQ3_17") (pintype "bidirectional"))
      (node (ref "XIO") (pin "6") (pinfunction "6_6") (pintype "passive"))
    )
    (net (code "71") (name "PA4") (class "Default")
      (node (ref "IC1") (pin "6") (pinfunction "5D_6") (pintype "input"))
      (node (ref "U1") (pin "18") (pinfunction "DQ4_18") (pintype "bidirectional"))
      (node (ref "XIO") (pin "7") (pinfunction "7_7") (pintype "passive"))
    )
    (net (code "72") (name "PA5") (class "Default")
      (node (ref "IC1") (pin "7") (pinfunction "6D_7") (pintype "input"))
      (node (ref "U1") (pin "19") (pinfunction "DQ5_19") (pintype "bidirectional"))
      (node (ref "XIO") (pin "8") (pinfunction "8_8") (pintype "passive"))
    )
    (net (code "73") (name "PA6") (class "Default")
      (node (ref "IC1") (pin "8") (pinfunction "7D_8") (pintype "input"))
      (node (ref "U1") (pin "20") (pinfunction "DQ6_20") (pintype "bidirectional"))
      (node (ref "XIO") (pin "9") (pinfunction "9_9") (pintype "passive"))
    )
    (net (code "74") (name "PA7") (class "Default")
      (node (ref "IC1") (pin "9") (pinfunction "8D_9") (pintype "input"))
      (node (ref "U1") (pin "21") (pinfunction "DQ7_21") (pintype "bidirectional"))
      (node (ref "XIO") (pin "10") (pinfunction "10_10") (pintype "passive"))
    )
    (net (code "75") (name "PB0") (class "Default")
      (node (ref "JP1") (pin "7") (pinfunction "7_7") (pintype "passive"))
      (node (ref "XIO") (pin "34") (pinfunction "34_34") (pintype "passive"))
    )
    (net (code "76") (name "PB1") (class "Default")
      (node (ref "IC4") (pin "7") (pinfunction "CI_7") (pintype "input"))
      (node (ref "JP1") (pin "4") (pinfunction "4_4") (pintype "passive"))
      (node (ref "XIO") (pin "33") (pinfunction "33_33") (pintype "passive"))
    )
    (net (code "77") (name "PB2") (class "Default")
      (node (ref "IC4") (pin "9") (pinfunction "DI_9") (pintype "input"))
      (node (ref "JP1") (pin "6") (pinfunction "6_6") (pintype "passive"))
      (node (ref "XIO") (pin "32") (pinfunction "32_32") (pintype "passive"))
    )
    (net (code "78") (name "PB3") (class "Default")
      (node (ref "JP1") (pin "5") (pinfunction "5_5") (pintype "passive"))
      (node (ref "XIO") (pin "31") (pinfunction "31_31") (pintype "passive"))
    )
    (net (code "79") (name "PB4") (class "Default")
      (node (ref "JP6") (pin "8") (pinfunction "8_8") (pintype "passive"))
    )
    (net (code "80") (name "PB5") (class "Default")
      (node (ref "JP6") (pin "7") (pinfunction "7_7") (pintype "passive"))
    )
    (net (code "81") (name "PB6") (class "Default")
      (node (ref "JP6") (pin "6") (pinfunction "6_6") (pintype "passive"))
    )
    (net (code "82") (name "PB7") (class "Default")
      (node (ref "JP6") (pin "5") (pinfunction "5_5") (pintype "passive"))
    )
    (net (code "83") (name "PC0") (class "Default")
      (node (ref "U1") (pin "27") (pinfunction "A8_27") (pintype "input"))
      (node (ref "XIO") (pin "18") (pinfunction "18_18") (pintype "passive"))
    )
    (net (code "84") (name "PC1") (class "Default")
      (node (ref "U1") (pin "26") (pinfunction "A9_26") (pintype "input"))
      (node (ref "XIO") (pin "17") (pinfunction "17_17") (pintype "passive"))
    )
    (net (code "85") (name "PC2") (class "Default")
      (node (ref "U1") (pin "23") (pinfunction "A10_23") (pintype "input"))
      (node (ref "XIO") (pin "16") (pinfunction "16_16") (pintype "passive"))
    )
    (net (code "86") (name "PC3") (class "Default")
      (node (ref "U1") (pin "25") (pinfunction "A11_25") (pintype "input"))
      (node (ref "XIO") (pin "15") (pinfunction "15_15") (pintype "passive"))
    )
    (net (code "87") (name "PC4") (class "Default")
      (node (ref "U1") (pin "4") (pinfunction "A12_4") (pintype "input"))
      (node (ref "XIO") (pin "14") (pinfunction "14_14") (pintype "passive"))
    )
    (net (code "88") (name "PC5") (class "Default")
      (node (ref "U1") (pin "28") (pinfunction "A13_28") (pintype "input"))
      (node (ref "XIO") (pin "13") (pinfunction "13_13") (pintype "passive"))
    )
    (net (code "89") (name "PC6") (class "Default")
      (node (ref "U1") (pin "3") (pinfunction "A14_3") (pintype "input"))
      (node (ref "XIO") (pin "12") (pinfunction "12_12") (pintype "passive"))
    )
    (net (code "90") (name "PC7") (class "Default")
      (node (ref "U1") (pin "31") (pinfunction "A15_31") (pintype "input"))
      (node (ref "XIO") (pin "11") (pinfunction "11_11") (pintype "passive"))
    )
    (net (code "91") (name "PD0") (class "Default")
      (node (ref "COMMUNICATION") (pin "1") (pinfunction "1_1") (pintype "passive"))
    )
    (net (code "92") (name "PD1") (class "Default")
      (node (ref "COMMUNICATION") (pin "2") (pinfunction "2_2") (pintype "passive"))
    )
    (net (code "93") (name "PD7") (class "Default")
      (node (ref "IC4") (pin "11") (pinfunction "EI_11") (pintype "input"))
      (node (ref "XIO") (pin "19") (pinfunction "19_19") (pintype "passive"))
    )
    (net (code "94") (name "PE0") (class "Default")
      (node (ref "PWML") (pin "1") (pinfunction "1_1") (pintype "passive"))
    )
    (net (code "95") (name "PE1") (class "Default")
      (node (ref "PWML") (pin "2") (pinfunction "2_2") (pintype "passive"))
    )
    (net (code "96") (name "PE3") (class "Default")
      (node (ref "PWML") (pin "6") (pinfunction "6_6") (pintype "passive"))
    )
    (net (code "97") (name "PE4") (class "Default")
      (node (ref "PWML") (pin "3") (pinfunction "3_3") (pintype "passive"))
      (node (ref "R3") (pin "1") (pinfunction "1_1") (pintype "passive"))
    )
    (net (code "98") (name "PE5") (class "Default")
      (node (ref "PWML") (pin "4") (pinfunction "4_4") (pintype "passive"))
      (node (ref "R4") (pin "1") (pinfunction "1_1") (pintype "passive"))
    )
    (net (code "99") (name "PG0") (class "Default")
      (node (ref "U1") (pin "29") (pinfunction "WE_29") (pintype "input"))
      (node (ref "XIO") (pin "22") (pinfunction "22_22") (pintype "passive"))
    )
    (net (code "100") (name "PG1") (class "Default")
      (node (ref "U1") (pin "24") (pinfunction "OE_24") (pintype "input"))
      (node (ref "XIO") (pin "21") (pinfunction "21_21") (pintype "passive"))
    )
    (net (code "101") (name "PG2") (class "Default")
      (node (ref "IC1") (pin "11") (pinfunction "C_11") (pintype "input"))
      (node (ref "XIO") (pin "20") (pinfunction "20_20") (pintype "passive"))
    )
    (net (code "102") (name "PG5") (class "Default")
      (node (ref "PWML") (pin "5") (pinfunction "5_5") (pintype "passive"))
    )
    (net (code "103") (name "PH3") (class "Default")
      (node (ref "PWML") (pin "7") (pinfunction "7_7") (pintype "passive"))
    )
    (net (code "104") (name "PH4") (class "Default")
      (node (ref "PWML") (pin "8") (pinfunction "8_8") (pintype "passive"))
    )
    (net (code "105") (name "PH5") (class "Default")
      (node (ref "JP6") (pin "10") (pinfunction "10_10") (pintype "passive"))
    )
    (net (code "106") (name "PH6") (class "Default")
      (node (ref "JP6") (pin "9") (pinfunction "9_9") (pintype "passive"))
    )
    (net (code "107") (name "PL0") (class "Default")
      (node (ref "IC3") (pin "9") (pinfunction "QH_9") (pintype "output"))
      (node (ref "XIO") (pin "30") (pinfunction "30_30") (pintype "passive"))
    )
    (net (code "108") (name "PL1") (class "Default")
      (node (ref "IC2") (pin "1") (pinfunction "SH/~{LD}_1") (pintype "input"))
      (node (ref "IC3") (pin "1") (pinfunction "SH/~{LD}_1") (pintype "input"))
      (node (ref "XIO") (pin "29") (pinfunction "29_29") (pintype "passive"))
    )
    (net (code "109") (name "PL2") (class "Default")
      (node (ref "IC2") (pin "2") (pinfunction "CLK_2") (pintype "input"))
      (node (ref "IC3") (pin "2") (pinfunction "CLK_2") (pintype "input"))
      (node (ref "XIO") (pin "28") (pinfunction "28_28") (pintype "passive"))
    )
    (net (code "110") (name "PL3") (class "Default")
      (node (ref "U$1") (pin "4") (pinfunction "RS_4") (pintype "input"))
      (node (ref "XIO") (pin "27") (pinfunction "27_27") (pintype "passive"))
    )
    (net (code "111") (name "PL4") (class "Default")
      (node (ref "U$1") (pin "6") (pinfunction "E_6") (pintype "input"))
      (node (ref "XIO") (pin "26") (pinfunction "26_26") (pintype "passive"))
    )
    (net (code "112") (name "PL5") (class "Default")
      (node (ref "IC4") (pin "3") (pinfunction "AI_3") (pintype "input"))
      (node (ref "XIO") (pin "25") (pinfunction "25_25") (pintype "passive"))
    )
    (net (code "113") (name "PL6") (class "Default")
      (node (ref "U1") (pin "2") (pinfunction "A16_2") (pintype "input"))
      (node (ref "XIO") (pin "24") (pinfunction "24_24") (pintype "passive"))
    )
    (net (code "114") (name "PL7") (class "Default")
      (node (ref "IC4") (pin "5") (pinfunction "BI_5") (pintype "input"))
      (node (ref "XIO") (pin "23") (pinfunction "23_23") (pintype "passive"))
    )
    (net (code "115") (name "RESET") (class "Default")
      (node (ref "POWER") (pin "3") (pinfunction "3_3") (pintype "passive"))
    )
    (net (code "116") (name "RXD1") (class "Default")
      (node (ref "COMMUNICATION") (pin "3") (pinfunction "3_3") (pintype "passive"))
      (node (ref "OK1") (pin "6") (pinfunction "VO_6") (pintype "passive"))
      (node (ref "R12") (pin "1") (pinfunction "1_1") (pintype "passive"))
    )
    (net (code "117") (name "RXD2") (class "Default")
      (node (ref "COMMUNICATION") (pin "5") (pinfunction "5_5") (pintype "passive"))
      (node (ref "OK2") (pin "6") (pinfunction "VO_6") (pintype "passive"))
      (node (ref "R11") (pin "1") (pinfunction "1_1") (pintype "passive"))
    )
    (net (code "118") (name "RXD3") (class "Default")
      (node (ref "COMMUNICATION") (pin "7") (pinfunction "7_7") (pintype "passive"))
    )
    (net (code "119") (name "SCL") (class "Default")
      (node (ref "JP6") (pin "1") (pinfunction "1_1") (pintype "passive"))
    )
    (net (code "120") (name "TXD1") (class "Default")
      (node (ref "COMMUNICATION") (pin "4") (pinfunction "4_4") (pintype "passive"))
      (node (ref "R8") (pin "2") (pinfunction "2_2") (pintype "passive"))
    )
    (net (code "121") (name "TXD2") (class "Default")
      (node (ref "COMMUNICATION") (pin "6") (pinfunction "6_6") (pintype "passive"))
      (node (ref "R9") (pin "2") (pinfunction "2_2") (pintype "passive"))
    )
    (net (code "122") (name "TXD3") (class "Default")
      (node (ref "COMMUNICATION") (pin "8") (pinfunction "8_8") (pintype "passive"))
    )
    (net (code "123") (name "VDD") (class "Default")
      (node (ref "IC4") (pin "16") (pinfunction "VDD_16") (pintype "power_in"))
    )
    (net (code "124") (name "VIN") (class "Default")
      (node (ref "POWER") (pin "8") (pinfunction "8_8") (pintype "passive"))
      (node (ref "S1") (pin "2") (pinfunction "P_2") (pintype "passive"))
    )
    (net (code "125") (name "unconnected-(IC2A-~{QH}-Pad7)") (class "Default")
      (node (ref "IC2") (pin "7") (pinfunction "~{QH}_7") (pintype "output"))
    )
    (net (code "126") (name "unconnected-(IC3A-~{QH}-Pad7)") (class "Default")
      (node (ref "IC3") (pin "7") (pinfunction "~{QH}_7") (pintype "output"))
    )
    (net (code "127") (name "unconnected-(IC4A-FI-Pad14)") (class "Default")
      (node (ref "IC4") (pin "14") (pinfunction "FI_14") (pintype "input"))
    )
    (net (code "128") (name "unconnected-(IC4A-FO-Pad15)") (class "Default")
      (node (ref "IC4") (pin "15") (pinfunction "FO_15") (pintype "output"))
    )
    (net (code "129") (name "unconnected-(IC4A-MODE-Pad13)") (class "Default")
      (node (ref "IC4") (pin "13") (pinfunction "MODE_13") (pintype "input"))
    )
    (net (code "130") (name "unconnected-(JP1-Pad2)") (class "Default")
      (node (ref "JP1") (pin "2") (pinfunction "2_2") (pintype "passive"))
    )
    (net (code "131") (name "unconnected-(OK1-VE-Pad7)") (class "Default")
      (node (ref "OK1") (pin "7") (pinfunction "VE_7") (pintype "passive"))
    )
    (net (code "132") (name "unconnected-(OK2-VE-Pad7)") (class "Default")
      (node (ref "OK2") (pin "7") (pinfunction "VE_7") (pintype "passive"))
    )
    (net (code "133") (name "unconnected-(POWER-Pad1)") (class "Default")
      (node (ref "POWER") (pin "1") (pinfunction "1_1") (pintype "passive"))
    )
    (net (code "134") (name "unconnected-(POWER-Pad2)") (class "Default")
      (node (ref "POWER") (pin "2") (pinfunction "2_2") (pintype "passive"))
    )
    (net (code "135") (name "unconnected-(S1-O-Pad1)") (class "Default")
      (node (ref "S1") (pin "1") (pinfunction "O_1") (pintype "passive"))
    )
    (net (code "136") (name "unconnected-(U$1-DB0-Pad7)") (class "Default")
      (node (ref "U$1") (pin "7") (pinfunction "DB0_7") (pintype "bidirectional"))
    )
    (net (code "137") (name "unconnected-(U$1-DB1-Pad8)") (class "Default")
      (node (ref "U$1") (pin "8") (pinfunction "DB1_8") (pintype "bidirectional"))
    )
    (net (code "138") (name "unconnected-(U$1-DB2-Pad9)") (class "Default")
      (node (ref "U$1") (pin "9") (pinfunction "DB2_9") (pintype "bidirectional"))
    )
    (net (code "139") (name "unconnected-(U$1-DB3-Pad10)") (class "Default")
      (node (ref "U$1") (pin "10") (pinfunction "DB3_10") (pintype "bidirectional"))
    )
    (net (code "140") (name "unconnected-(U$2-PadP$3)") (class "Default")
      (node (ref "U$2") (pin "P$3") (pinfunction "P$3_P$3") (pintype "bidirectional"))
    )
    (net (code "141") (name "unconnected-(U$2-PadP$5)") (class "Default")
      (node (ref "U$2") (pin "P$5") (pinfunction "P$5_P$5") (pintype "bidirectional"))
    )
    (net (code "142") (name "unconnected-(U$2-PadP$6)") (class "Default")
      (node (ref "U$2") (pin "P$6") (pinfunction "P$6_P$6") (pintype "bidirectional"))
    )
    (net (code "143") (name "unconnected-(U$2-PadP$9)") (class "Default")
      (node (ref "U$2") (pin "P$9") (pinfunction "P$9_P$9") (pintype "bidirectional"))
    )
    (net (code "144") (name "unconnected-(U$2-PadP$10)") (class "Default")
      (node (ref "U$2") (pin "P$10") (pinfunction "P$10_P$10") (pintype "bidirectional"))
    )
    (net (code "145") (name "unconnected-(U$2-PadP$11)") (class "Default")
      (node (ref "U$2") (pin "P$11") (pinfunction "P$11_P$11") (pintype "bidirectional"))
    )
    (net (code "146") (name "unconnected-(U$2-PadP$12)") (class "Default")
      (node (ref "U$2") (pin "P$12") (pinfunction "P$12_P$12") (pintype "bidirectional"))
    )
    (net (code "147") (name "unconnected-(U$2-PadP$13)") (class "Default")
      (node (ref "U$2") (pin "P$13") (pinfunction "P$13_P$13") (pintype "bidirectional"))
    )
    (net (code "148") (name "unconnected-(U$2-PadP$14)") (class "Default")
      (node (ref "U$2") (pin "P$14") (pinfunction "P$14_P$14") (pintype "bidirectional"))
    )
    (net (code "149") (name "unconnected-(U$2-PadP$17)") (class "Default")
      (node (ref "U$2") (pin "P$17") (pinfunction "P$17_P$17") (pintype "bidirectional"))
    )
    (net (code "150") (name "unconnected-(U$2-PadP$18)") (class "Default")
      (node (ref "U$2") (pin "P$18") (pinfunction "P$18_P$18") (pintype "bidirectional"))
    )
    (net (code "151") (name "unconnected-(U$2-PadP$19)") (class "Default")
      (node (ref "U$2") (pin "P$19") (pinfunction "P$19_P$19") (pintype "bidirectional"))
    )
    (net (code "152") (name "unconnected-(U$2-PadP$20)") (class "Default")
      (node (ref "U$2") (pin "P$20") (pinfunction "P$20_P$20") (pintype "bidirectional"))
    )
    (net (code "153") (name "unconnected-(U$7-Pad1)") (class "Default")
      (node (ref "U$7") (pin "1") (pinfunction "1_1") (pintype "passive"))
    )
    (net (code "154") (name "unconnected-(U$7-Pad3)") (class "Default")
      (node (ref "U$7") (pin "3") (pinfunction "3_3") (pintype "passive"))
    )
    (net (code "155") (name "unconnected-(U$8-Pad1)") (class "Default")
      (node (ref "U$8") (pin "1") (pinfunction "1_1") (pintype "passive"))
    )
    (net (code "156") (name "unconnected-(U$8-Pad2)") (class "Default")
      (node (ref "U$8") (pin "2") (pinfunction "2_2") (pintype "passive"))
    )
    (net (code "157") (name "unconnected-(U$8-Pad3)") (class "Default")
      (node (ref "U$8") (pin "3") (pinfunction "3_3") (pintype "passive"))
    )
    (net (code "158") (name "unconnected-(U$9-Pad1)") (class "Default")
      (node (ref "U$9") (pin "1") (pinfunction "1_1") (pintype "passive"))
    )
    (net (code "159") (name "unconnected-(U$9-Pad3)") (class "Default")
      (node (ref "U$9") (pin "3") (pinfunction "3_3") (pintype "passive"))
    )
    (net (code "160") (name "unconnected-(U$10-Pad1)") (class "Default")
      (node (ref "U$10") (pin "1") (pinfunction "1_1") (pintype "passive"))
    )
    (net (code "161") (name "unconnected-(U$10-Pad2)") (class "Default")
      (node (ref "U$10") (pin "2") (pinfunction "2_2") (pintype "passive"))
    )
    (net (code "162") (name "unconnected-(U$10-Pad3)") (class "Default")
      (node (ref "U$10") (pin "3") (pinfunction "3_3") (pintype "passive"))
    )
    (net (code "163") (name "unconnected-(U1-NC-Pad1)") (class "Default")
      (node (ref "U1") (pin "1") (pinfunction "NC_1") (pintype "no_connect"))
    )
    (net (code "164") (name "unconnected-(XIO-Pad1)") (class "Default")
      (node (ref "XIO") (pin "1") (pinfunction "1_1") (pintype "passive"))
    )
    (net (code "165") (name "unconnected-(XIO-Pad2)") (class "Default")
      (node (ref "XIO") (pin "2") (pinfunction "2_2") (pintype "passive"))
    )
  )
)
